# SCH.net
KiCad netlist of a schematic drawn in EasyEDA
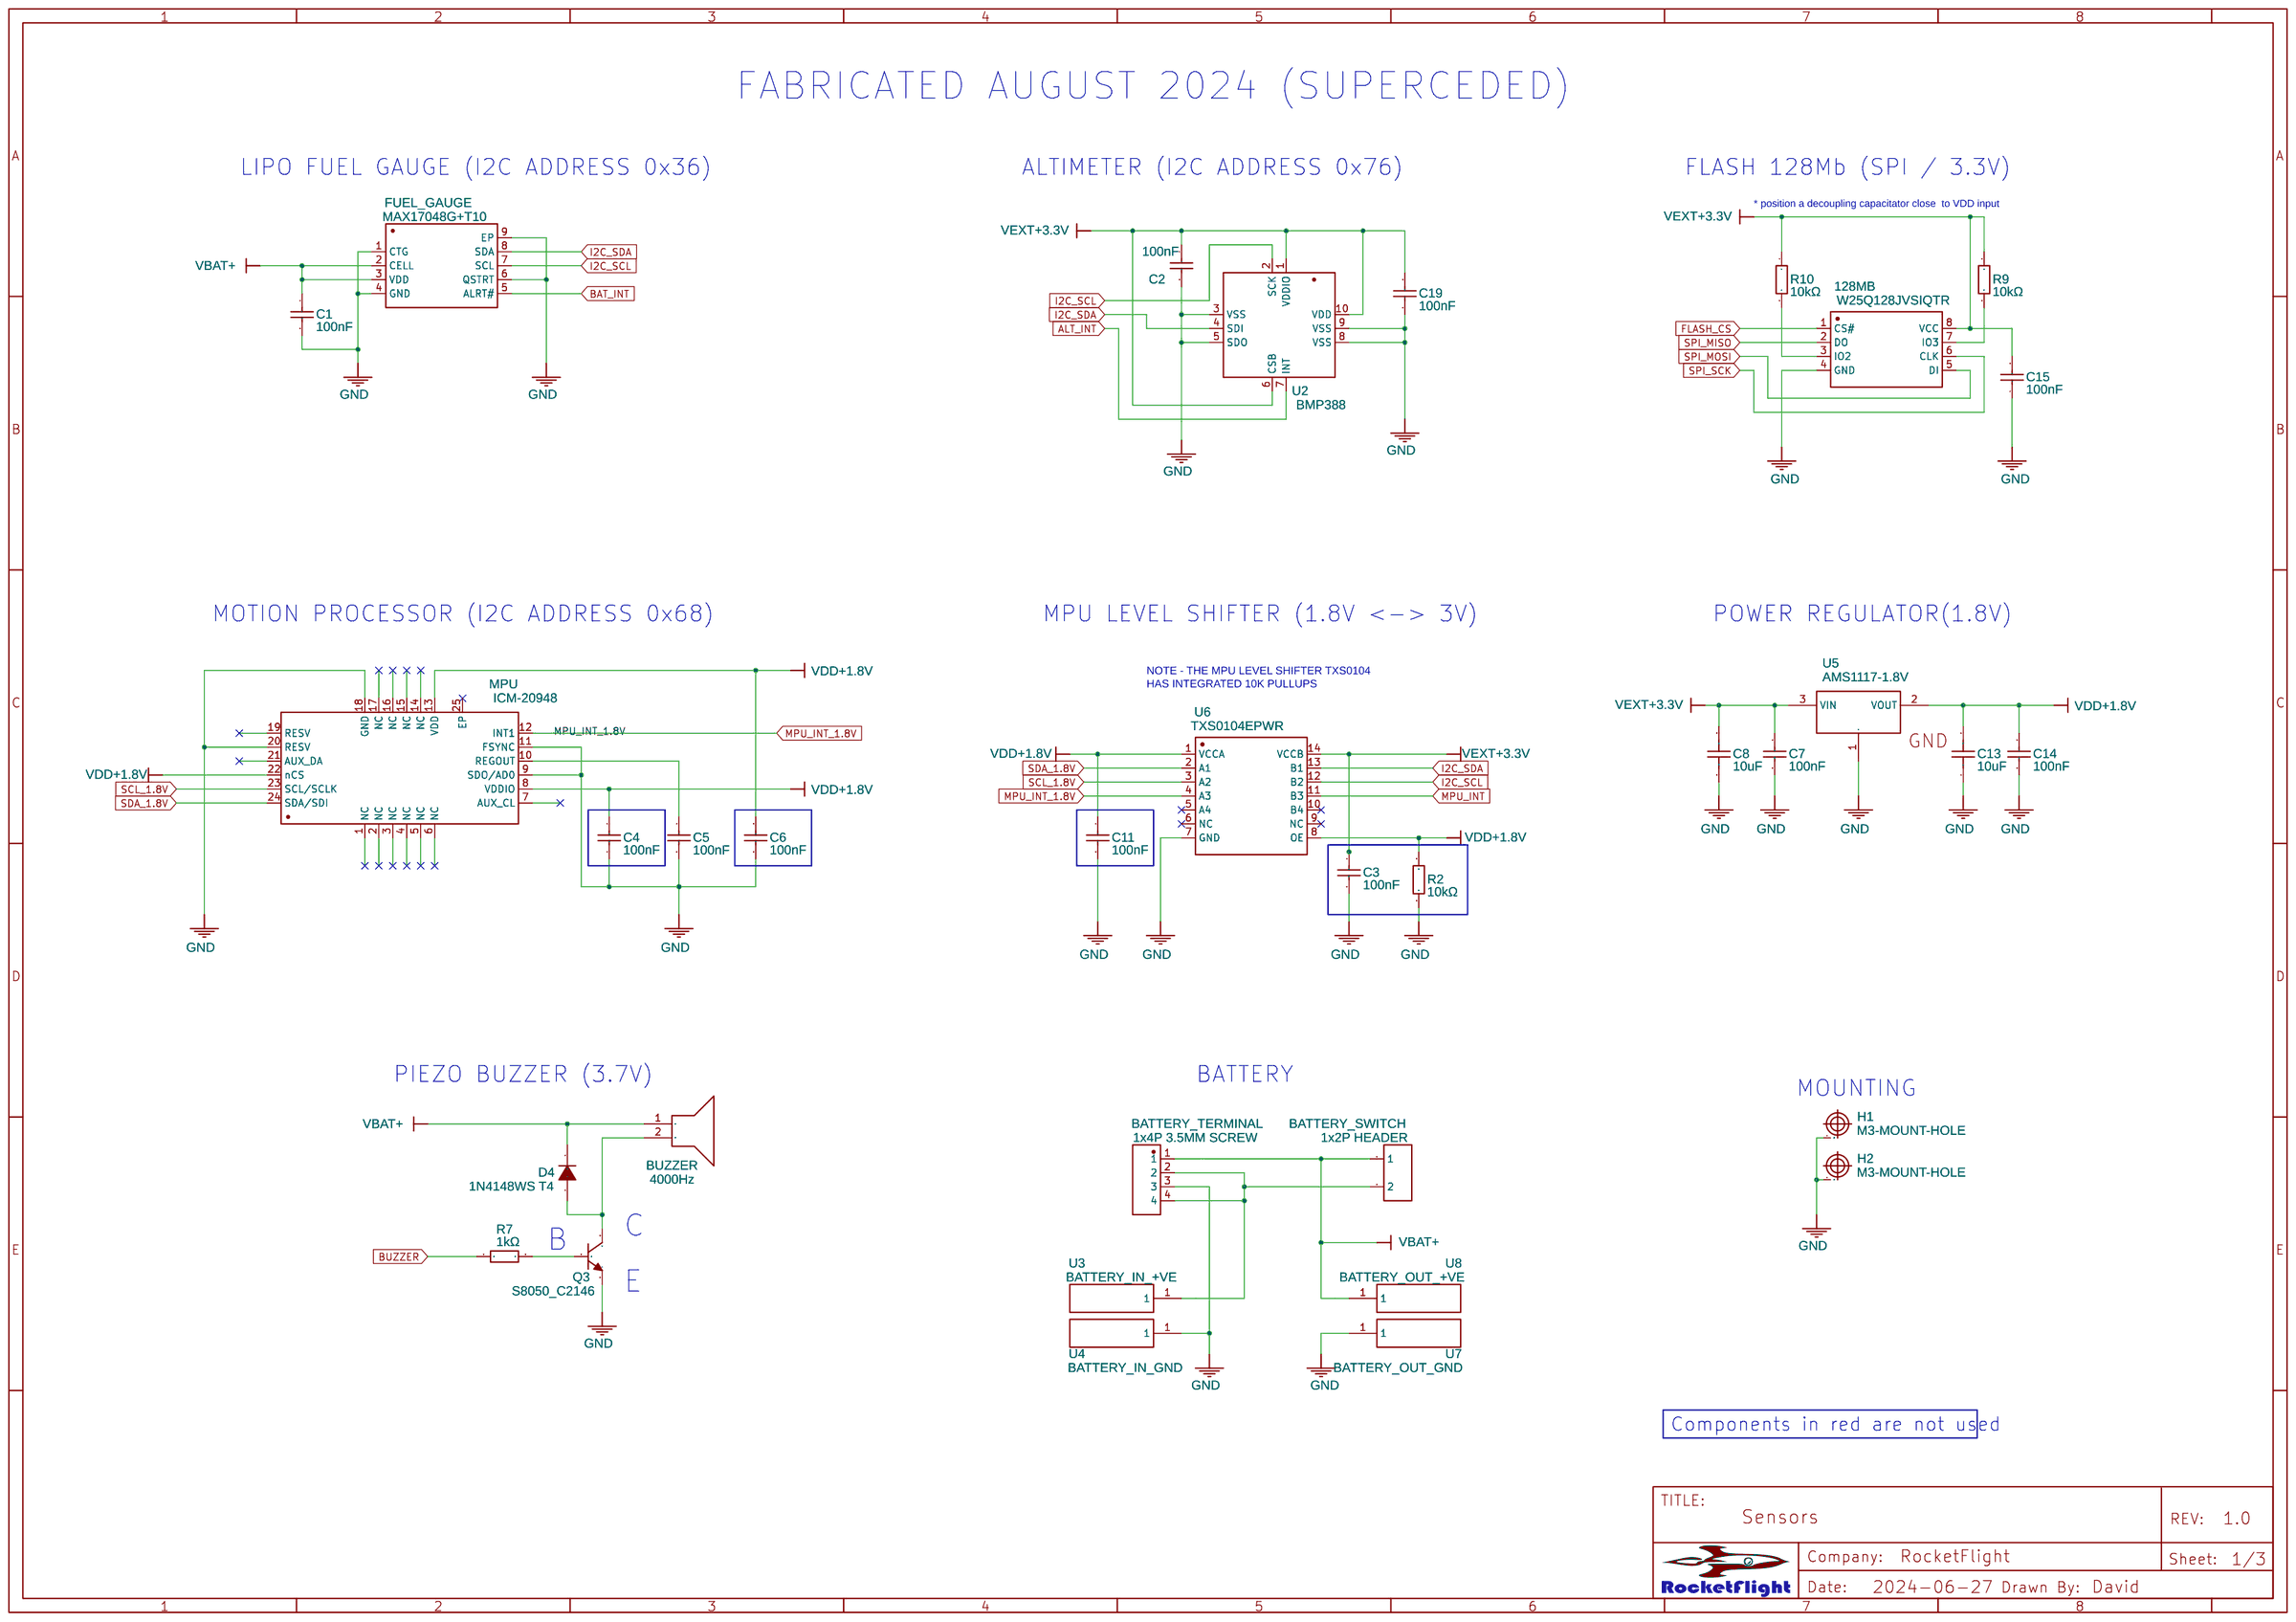
[diagram p0: Sensors]
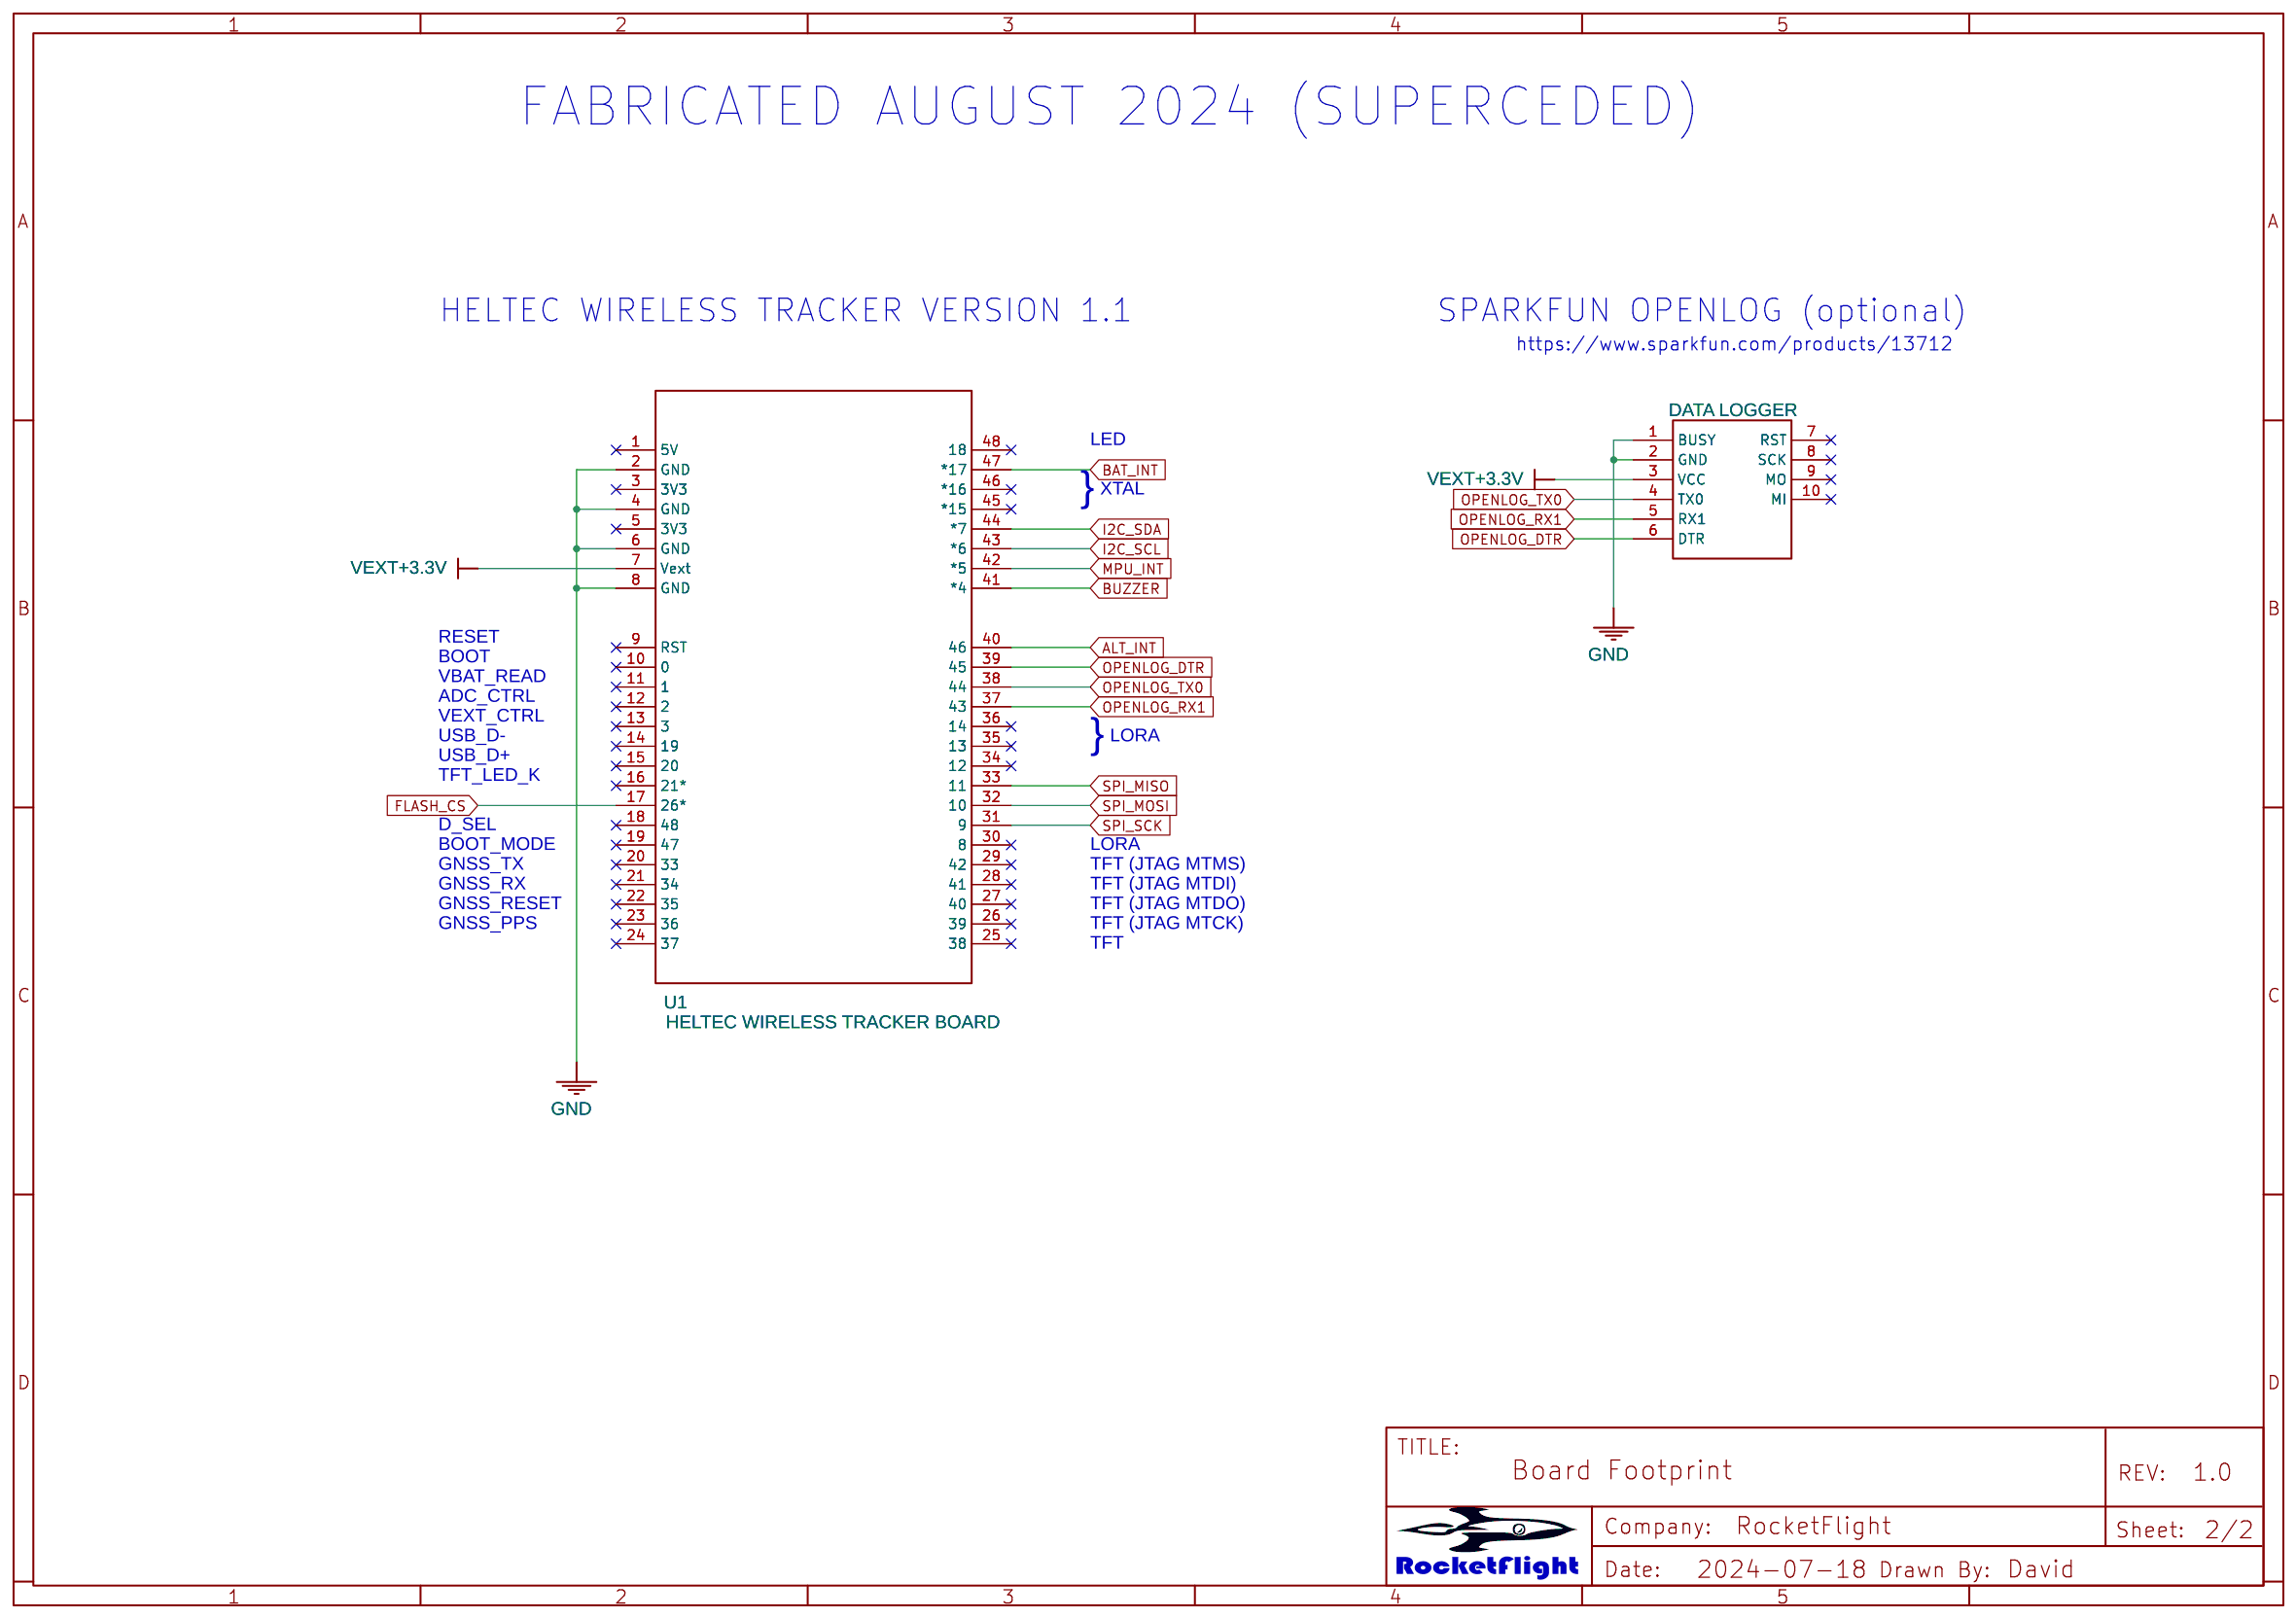
[diagram p1: Board]

(export (version "E")
  (design (tool "Eeschema 10.0.6"))
  (components
    (comp (ref "128MB")
      (value "W25Q128JVSIQTR")
      (fields (field (name "Manufacturer Part") "W25Q128JVSIQ") (field (name "Manufacturer") "WINBOND(华邦)"))
      (libsource (lib "") (part "W25Q128JVSIQTR"))
    )
    (comp (ref "BATTERY_SWITCH")
      (value "1x2P HEADER")
      (fields (field (name "Manufacturer Part") "826629-2") (field (name "Manufacturer") "TE Connectivity"))
      (libsource (lib "") (part "HDR-M-2.54_1X2_ROUND"))
    )
    (comp (ref "BATTERY_TERMINAL")
      (value "1x4P 3.5MM SCREW")
      (fields (field (name "Manufacturer Part") "XY350V-3.5-4P") (field (name "Manufacturer") "--"))
      (libsource (lib "") (part "XY350V-3.5-4P"))
    )
    (comp (ref "BUZZER")
      (value "4000Hz")
      (fields (field (name "Manufacturer Part") "FUET-9018") (field (name "Manufacturer") "FUET(福声科技)"))
      (libsource (lib "") (part "FST-9018 COPY"))
    )
    (comp (ref "C1")
      (value "100nF")
      (fields
        (field (name "Manufacturer Part") "CL05B104KO5NNNC")
        (field (name "Manufacturer") "SAMSUNG(三星)")
      )
      (libsource (lib "") (part "CL05B104KO5NNNC"))
    )
    (comp (ref "C2")
      (value "100nF")
      (fields
        (field (name "Manufacturer Part") "CL05B104KO5NNNC")
        (field (name "Manufacturer") "SAMSUNG(三星)")
      )
      (libsource (lib "") (part "CL05B104KO5NNNC"))
    )
    (comp (ref "C3")
      (value "100nF")
      (fields
        (field (name "Manufacturer Part") "CL05B104KO5NNNC")
        (field (name "Manufacturer") "SAMSUNG(三星)")
      )
      (libsource (lib "") (part "CL05B104KO5NNNC"))
    )
    (comp (ref "C4")
      (value "100nF")
      (fields
        (field (name "Manufacturer Part") "CL05B104KO5NNNC")
        (field (name "Manufacturer") "SAMSUNG(三星)")
      )
      (libsource (lib "") (part "CL05B104KO5NNNC_1"))
    )
    (comp (ref "C5")
      (value "100nF")
      (fields
        (field (name "Manufacturer Part") "CL05B104KO5NNNC")
        (field (name "Manufacturer") "SAMSUNG(三星)")
      )
      (libsource (lib "") (part "CL05B104KO5NNNC"))
    )
    (comp (ref "C6")
      (value "100nF")
      (fields
        (field (name "Manufacturer Part") "CL05B104KO5NNNC")
        (field (name "Manufacturer") "SAMSUNG(三星)")
      )
      (libsource (lib "") (part "CL05B104KO5NNNC_1"))
    )
    (comp (ref "C7")
      (value "100nF")
      (fields
        (field (name "Manufacturer Part") "CL05B104KO5NNNC")
        (field (name "Manufacturer") "SAMSUNG(三星)")
      )
      (libsource (lib "") (part "CL05B104KO5NNNC_1"))
    )
    (comp (ref "C8")
      (value "10uF")
      (fields
        (field (name "Manufacturer Part") "CL10A106MA8NRNC")
        (field (name "Manufacturer") "SAMSUNG(三星)")
      )
      (libsource (lib "") (part "CL10A106MA8NRNC"))
    )
    (comp (ref "C11")
      (value "100nF")
      (fields
        (field (name "Manufacturer Part") "CL05B104KO5NNNC")
        (field (name "Manufacturer") "SAMSUNG(三星)")
      )
      (libsource (lib "") (part "CL05B104KO5NNNC"))
    )
    (comp (ref "C13")
      (value "10uF")
      (fields
        (field (name "Manufacturer Part") "CL10A106MA8NRNC")
        (field (name "Manufacturer") "SAMSUNG(三星)")
      )
      (libsource (lib "") (part "CL10A106MA8NRNC"))
    )
    (comp (ref "C14")
      (value "100nF")
      (fields
        (field (name "Manufacturer Part") "CL05B104KO5NNNC")
        (field (name "Manufacturer") "SAMSUNG(三星)")
      )
      (libsource (lib "") (part "CL05B104KO5NNNC_1"))
    )
    (comp (ref "C15")
      (value "100nF")
      (fields
        (field (name "Manufacturer Part") "CL05B104KO5NNNC")
        (field (name "Manufacturer") "SAMSUNG(三星)")
      )
      (libsource (lib "") (part "CL05B104KO5NNNC_1"))
    )
    (comp (ref "C19")
      (value "100nF")
      (fields
        (field (name "Manufacturer Part") "CL05B104KO5NNNC")
        (field (name "Manufacturer") "SAMSUNG(三星)")
      )
      (libsource (lib "") (part "CL05B104KO5NNNC"))
    )
    (comp (ref "D4")
      (value "1N4148WS T4")
      (fields (field (name "Manufacturer Part") "1N4148WS") (field (name "Manufacturer") "CJ(江苏长电/长晶)"))
      (libsource (lib "") (part "1N4148WS T4"))
    )
    (comp (ref "FUEL_GAUGE")
      (value "MAX17048G+T10")
      (fields (field (name "Manufacturer") "ADI(亚德诺)/MAXIM(美信)"))
      (libsource (lib "") (part "MAX17048G+T10"))
    )
    (comp (ref "H1") (value "M3-MOUNT-HOLE") (libsource (lib "") (part "M3-MOUNT-HOLE")))
    (comp (ref "H2") (value "M3-MOUNT-HOLE") (libsource (lib "") (part "M3-MOUNT-HOLE")))
    (comp (ref "MPU")
      (value "ICM-20948")
      (fields (field (name "Manufacturer") "TDK InvenSense(应美盛)"))
      (libsource (lib "") (part "ICM-20948"))
    )
    (comp (ref "Q3")
      (value "S8050_C2146")
      (fields (field (name "Manufacturer Part") "S8050 J3Y") (field (name "Manufacturer") "CJ(江苏长电/长晶)"))
      (libsource (lib "") (part "S8050_C2146"))
    )
    (comp (ref "R2")
      (value "10kΩ")
      (fields
        (field (name "Manufacturer Part") "0402WGF1002TCE")
        (field (name "Manufacturer") "UNI-ROYAL(厚声)")
      )
      (libsource (lib "") (part "0402WGF1002TCE_1"))
    )
    (comp (ref "R7")
      (value "1kΩ")
      (fields
        (field (name "Manufacturer Part") "0603WAF1001T5E")
        (field (name "Manufacturer") "UNI-ROYAL(厚声)")
      )
      (libsource (lib "") (part "0603WAF1001T5E"))
    )
    (comp (ref "R9")
      (value "10kΩ")
      (fields
        (field (name "Manufacturer Part") "0402WGF1002TCE")
        (field (name "Manufacturer") "UNI-ROYAL(厚声)")
      )
      (libsource (lib "") (part "0402WGF1002TCE"))
    )
    (comp (ref "R10")
      (value "10kΩ")
      (fields
        (field (name "Manufacturer Part") "0402WGF1002TCE")
        (field (name "Manufacturer") "UNI-ROYAL(厚声)")
      )
      (libsource (lib "") (part "0402WGF1002TCE"))
    )
    (comp (ref "U2")
      (value "BMP388")
      (fields (field (name "Manufacturer") "Bosch(博世)"))
      (libsource (lib "") (part "BMP388"))
    )
    (comp (ref "U3")
      (value "BATTERY_IN_+VE")
      (fields (field (name "Manufacturer Part") "PAD_5.84mm×1.54mm×0.8mm"))
      (libsource (lib "") (part "MySolderPad1.5x2.5mm"))
    )
    (comp (ref "U4")
      (value "BATTERY_IN_GND")
      (fields (field (name "Manufacturer Part") "PAD_5.84mm×1.54mm×0.8mm"))
      (libsource (lib "") (part "MySolderPad1.5x2.5mm"))
    )
    (comp (ref "U5")
      (value "AMS1117-1.8V")
      (fields (field (name "Manufacturer") "MSKSEMI(美森科)"))
      (libsource (lib "") (part "AMS1117-1.8V"))
    )
    (comp (ref "U6")
      (value "TXS0104EPWR")
      (fields (field (name "Manufacturer") "TI(德州仪器)"))
      (libsource (lib "") (part "TXS0104EPWR"))
    )
    (comp (ref "U7")
      (value "BATTERY_OUT_GND")
      (fields (field (name "Manufacturer Part") "PAD_5.84mm×1.54mm×0.8mm"))
      (libsource (lib "") (part "MySolderPad1.5x2.5mm_1"))
    )
    (comp (ref "U8")
      (value "BATTERY_OUT_+VE")
      (fields (field (name "Manufacturer Part") "PAD_5.84mm×1.54mm×0.8mm"))
      (libsource (lib "") (part "MySolderPad1.5x2.5mm_1"))
    )
    (comp (ref "BUSY")
      (value "DATA LOGGER")
      (fields (field (name "Manufacturer Part") "Sparkfun"))
      (libsource (lib "") (part "DATA LOGGER_RN_OPENLOG COPY"))
    )
    (comp (ref "U1")
      (value "HELTEC WIRELESS TRACKER BOARD")
      (libsource (lib "") (part "HELTEC WIRELESS TRACKER BOARD"))
    )
  )
  (nets
    (net (code "1") (name "ALT_INT") (class "Default")
      (node (ref "U1") (pin "40") (pinfunction "46_40") (pintype "unspecified"))
      (node (ref "U2") (pin "7") (pinfunction "INT_7") (pintype "unspecified"))
    )
    (net (code "2") (name "BAT_INT") (class "Default")
      (node (ref "FUEL_GAUGE") (pin "5") (pinfunction "ALRT#_5") (pintype "unspecified"))
      (node (ref "U1") (pin "47") (pinfunction "*17_47") (pintype "unspecified"))
    )
    (net (code "3") (name "BUZZER") (class "Default")
      (node (ref "R7") (pin "1") (pinfunction "1_1") (pintype "input"))
      (node (ref "U1") (pin "41") (pinfunction "*4_41") (pintype "unspecified"))
    )
    (net (code "4") (name "FLASH_CS") (class "Default")
      (node (ref "128MB") (pin "1") (pinfunction "CS#_1") (pintype "unspecified"))
      (node (ref "U1") (pin "17") (pinfunction "26*_17") (pintype "unspecified"))
    )
    (net (code "5") (name "GND") (class "Default")
      (node (ref "128MB") (pin "4") (pinfunction "GND_4") (pintype "unspecified"))
      (node (ref "BATTERY_TERMINAL") (pin "3") (pinfunction "3_3") (pintype "unspecified"))
      (node (ref "BUSY") (pin "1") (pinfunction "BUSY_1") (pintype "unspecified"))
      (node (ref "BUSY") (pin "2") (pinfunction "GND_2") (pintype "unspecified"))
      (node (ref "C1") (pin "2") (pinfunction "2_2") (pintype "input"))
      (node (ref "C11") (pin "2") (pinfunction "2_2") (pintype "input"))
      (node (ref "C13") (pin "1") (pinfunction "1_1") (pintype "unspecified"))
      (node (ref "C14") (pin "1") (pinfunction "1_1") (pintype "input"))
      (node (ref "C15") (pin "1") (pinfunction "1_1") (pintype "input"))
      (node (ref "C19") (pin "2") (pinfunction "2_2") (pintype "input"))
      (node (ref "C2") (pin "2") (pinfunction "2_2") (pintype "input"))
      (node (ref "C3") (pin "2") (pinfunction "2_2") (pintype "input"))
      (node (ref "C4") (pin "1") (pinfunction "1_1") (pintype "input"))
      (node (ref "C5") (pin "2") (pinfunction "2_2") (pintype "input"))
      (node (ref "C6") (pin "1") (pinfunction "1_1") (pintype "input"))
      (node (ref "C7") (pin "1") (pinfunction "1_1") (pintype "input"))
      (node (ref "C8") (pin "1") (pinfunction "1_1") (pintype "unspecified"))
      (node (ref "FUEL_GAUGE") (pin "1") (pinfunction "CTG_1") (pintype "unspecified"))
      (node (ref "FUEL_GAUGE") (pin "4") (pinfunction "GND_4") (pintype "unspecified"))
      (node (ref "FUEL_GAUGE") (pin "6") (pinfunction "QSTRT_6") (pintype "unspecified"))
      (node (ref "FUEL_GAUGE") (pin "9") (pinfunction "EP_9") (pintype "unspecified"))
      (node (ref "H1") (pin "1") (pinfunction "GND_1") (pintype "passive"))
      (node (ref "H2") (pin "1") (pinfunction "GND_1") (pintype "passive"))
      (node (ref "MPU") (pin "11") (pinfunction "FSYNC_11") (pintype "unspecified"))
      (node (ref "MPU") (pin "18") (pinfunction "GND_18") (pintype "unspecified"))
      (node (ref "MPU") (pin "20") (pinfunction "RESV_20") (pintype "unspecified"))
      (node (ref "MPU") (pin "9") (pinfunction "SDO/AD0_9") (pintype "unspecified"))
      (node (ref "Q3") (pin "2") (pinfunction "E_2") (pintype "unspecified"))
      (node (ref "R2") (pin "1") (pinfunction "1_1") (pintype "input"))
      (node (ref "U1") (pin "2") (pinfunction "GND_2") (pintype "unspecified"))
      (node (ref "U1") (pin "4") (pinfunction "GND_4") (pintype "unspecified"))
      (node (ref "U1") (pin "6") (pinfunction "GND_6") (pintype "unspecified"))
      (node (ref "U1") (pin "8") (pinfunction "GND_8") (pintype "unspecified"))
      (node (ref "U2") (pin "3") (pinfunction "VSS_3") (pintype "unspecified"))
      (node (ref "U2") (pin "5") (pinfunction "SDO_5") (pintype "unspecified"))
      (node (ref "U2") (pin "8") (pinfunction "VSS_8") (pintype "unspecified"))
      (node (ref "U2") (pin "9") (pinfunction "VSS_9") (pintype "unspecified"))
      (node (ref "U4") (pin "1") (pinfunction "1_1") (pintype "unspecified"))
      (node (ref "U5") (pin "1") (pinfunction "GND_1") (pintype "passive"))
      (node (ref "U6") (pin "7") (pinfunction "GND_7") (pintype "unspecified"))
      (node (ref "U7") (pin "1") (pinfunction "1_1") (pintype "unspecified"))
    )
    (net (code "6") (name "I2C_SCL") (class "Default")
      (node (ref "FUEL_GAUGE") (pin "7") (pinfunction "SCL_7") (pintype "unspecified"))
      (node (ref "U1") (pin "43") (pinfunction "*6_43") (pintype "unspecified"))
      (node (ref "U2") (pin "2") (pinfunction "SCK_2") (pintype "unspecified"))
      (node (ref "U6") (pin "12") (pinfunction "B2_12") (pintype "unspecified"))
    )
    (net (code "7") (name "I2C_SDA") (class "Default")
      (node (ref "FUEL_GAUGE") (pin "8") (pinfunction "SDA_8") (pintype "unspecified"))
      (node (ref "U1") (pin "44") (pinfunction "*7_44") (pintype "unspecified"))
      (node (ref "U2") (pin "4") (pinfunction "SDI_4") (pintype "unspecified"))
      (node (ref "U6") (pin "13") (pinfunction "B1_13") (pintype "unspecified"))
    )
    (net (code "8") (name "MPU_INT") (class "Default")
      (node (ref "U1") (pin "42") (pinfunction "*5_42") (pintype "unspecified"))
      (node (ref "U6") (pin "11") (pinfunction "B3_11") (pintype "unspecified"))
    )
    (net (code "9") (name "MPU_INT_1.8V") (class "Default")
      (node (ref "MPU") (pin "12") (pinfunction "INT1_12") (pintype "unspecified"))
      (node (ref "U6") (pin "4") (pinfunction "A3_4") (pintype "unspecified"))
    )
    (net (code "10") (name "Net-(128MB-IO2)") (class "Default")
      (node (ref "128MB") (pin "3") (pinfunction "IO2_3") (pintype "unspecified"))
      (node (ref "R10") (pin "2") (pinfunction "2_2") (pintype "input"))
    )
    (net (code "11") (name "Net-(128MB-IO3)") (class "Default")
      (node (ref "128MB") (pin "7") (pinfunction "IO3_7") (pintype "unspecified"))
      (node (ref "R9") (pin "2") (pinfunction "2_2") (pintype "input"))
    )
    (net (code "12") (name "Net-(BATTERY_SWITCH-Pad2)") (class "Default")
      (node (ref "BATTERY_SWITCH") (pin "2") (pinfunction "2_2") (pintype "unspecified"))
      (node (ref "BATTERY_TERMINAL") (pin "2") (pinfunction "2_2") (pintype "unspecified"))
      (node (ref "BATTERY_TERMINAL") (pin "4") (pinfunction "4_4") (pintype "unspecified"))
      (node (ref "U3") (pin "1") (pinfunction "1_1") (pintype "unspecified"))
    )
    (net (code "13") (name "Net-(D4-A)") (class "Default")
      (node (ref "BUZZER") (pin "2") (pinfunction "2_2") (pintype "unspecified"))
      (node (ref "D4") (pin "2") (pinfunction "A_2") (pintype "unspecified"))
      (node (ref "Q3") (pin "3") (pinfunction "C_3") (pintype "unspecified"))
    )
    (net (code "14") (name "Net-(MPU-REGOUT)") (class "Default")
      (node (ref "C5") (pin "1") (pinfunction "1_1") (pintype "input"))
      (node (ref "MPU") (pin "10") (pinfunction "REGOUT_10") (pintype "unspecified"))
    )
    (net (code "15") (name "Net-(Q3-B)") (class "Default")
      (node (ref "Q3") (pin "1") (pinfunction "B_1") (pintype "unspecified"))
      (node (ref "R7") (pin "2") (pinfunction "2_2") (pintype "input"))
    )
    (net (code "16") (name "OPENLOG_DTR") (class "Default")
      (node (ref "BUSY") (pin "6") (pinfunction "DTR_6") (pintype "unspecified"))
      (node (ref "U1") (pin "39") (pinfunction "45_39") (pintype "unspecified"))
    )
    (net (code "17") (name "OPENLOG_RX1") (class "Default")
      (node (ref "BUSY") (pin "5") (pinfunction "RX1_5") (pintype "unspecified"))
      (node (ref "U1") (pin "37") (pinfunction "43_37") (pintype "unspecified"))
    )
    (net (code "18") (name "OPENLOG_TX0") (class "Default")
      (node (ref "BUSY") (pin "4") (pinfunction "TX0_4") (pintype "unspecified"))
      (node (ref "U1") (pin "38") (pinfunction "44_38") (pintype "unspecified"))
    )
    (net (code "19") (name "SCL_1.8V") (class "Default")
      (node (ref "MPU") (pin "23") (pinfunction "SCL/SCLK_23") (pintype "unspecified"))
      (node (ref "U6") (pin "3") (pinfunction "A2_3") (pintype "unspecified"))
    )
    (net (code "20") (name "SDA_1.8V") (class "Default")
      (node (ref "MPU") (pin "24") (pinfunction "SDA/SDI_24") (pintype "unspecified"))
      (node (ref "U6") (pin "2") (pinfunction "A1_2") (pintype "unspecified"))
    )
    (net (code "21") (name "SPI_MISO") (class "Default")
      (node (ref "128MB") (pin "2") (pinfunction "DO_2") (pintype "unspecified"))
      (node (ref "U1") (pin "33") (pinfunction "11_33") (pintype "unspecified"))
    )
    (net (code "22") (name "SPI_MOSI") (class "Default")
      (node (ref "128MB") (pin "5") (pinfunction "DI_5") (pintype "unspecified"))
      (node (ref "U1") (pin "32") (pinfunction "10_32") (pintype "unspecified"))
    )
    (net (code "23") (name "SPI_SCK") (class "Default")
      (node (ref "128MB") (pin "6") (pinfunction "CLK_6") (pintype "unspecified"))
      (node (ref "U1") (pin "31") (pinfunction "9_31") (pintype "unspecified"))
    )
    (net (code "24") (name "VBAT+") (class "Default")
      (node (ref "BATTERY_SWITCH") (pin "1") (pinfunction "1_1") (pintype "unspecified"))
      (node (ref "BATTERY_TERMINAL") (pin "1") (pinfunction "1_1") (pintype "unspecified"))
      (node (ref "BUZZER") (pin "1") (pinfunction "1_1") (pintype "unspecified"))
      (node (ref "C1") (pin "1") (pinfunction "1_1") (pintype "input"))
      (node (ref "D4") (pin "1") (pinfunction "K_1") (pintype "unspecified"))
      (node (ref "FUEL_GAUGE") (pin "2") (pinfunction "CELL_2") (pintype "unspecified"))
      (node (ref "FUEL_GAUGE") (pin "3") (pinfunction "VDD_3") (pintype "unspecified"))
      (node (ref "U8") (pin "1") (pinfunction "1_1") (pintype "unspecified"))
    )
    (net (code "25") (name "VDD+1.8V") (class "Default")
      (node (ref "C11") (pin "1") (pinfunction "1_1") (pintype "input"))
      (node (ref "C13") (pin "2") (pinfunction "2_2") (pintype "unspecified"))
      (node (ref "C14") (pin "2") (pinfunction "2_2") (pintype "input"))
      (node (ref "C4") (pin "2") (pinfunction "2_2") (pintype "input"))
      (node (ref "C6") (pin "2") (pinfunction "2_2") (pintype "input"))
      (node (ref "MPU") (pin "13") (pinfunction "VDD_13") (pintype "unspecified"))
      (node (ref "MPU") (pin "22") (pinfunction "nCS_22") (pintype "unspecified"))
      (node (ref "MPU") (pin "8") (pinfunction "VDDIO_8") (pintype "unspecified"))
      (node (ref "R2") (pin "2") (pinfunction "2_2") (pintype "input"))
      (node (ref "U5") (pin "2") (pinfunction "VOUT_2") (pintype "passive"))
      (node (ref "U6") (pin "1") (pinfunction "VCCA_1") (pintype "unspecified"))
      (node (ref "U6") (pin "8") (pinfunction "OE_8") (pintype "unspecified"))
    )
    (net (code "26") (name "VEXT+3.3V") (class "Default")
      (node (ref "128MB") (pin "8") (pinfunction "VCC_8") (pintype "unspecified"))
      (node (ref "BUSY") (pin "3") (pinfunction "VCC_3") (pintype "unspecified"))
      (node (ref "C15") (pin "2") (pinfunction "2_2") (pintype "input"))
      (node (ref "C19") (pin "1") (pinfunction "1_1") (pintype "input"))
      (node (ref "C2") (pin "1") (pinfunction "1_1") (pintype "input"))
      (node (ref "C3") (pin "1") (pinfunction "1_1") (pintype "input"))
      (node (ref "C7") (pin "2") (pinfunction "2_2") (pintype "input"))
      (node (ref "C8") (pin "2") (pinfunction "2_2") (pintype "unspecified"))
      (node (ref "R10") (pin "1") (pinfunction "1_1") (pintype "input"))
      (node (ref "R9") (pin "1") (pinfunction "1_1") (pintype "input"))
      (node (ref "U1") (pin "7") (pinfunction "Vext_7") (pintype "unspecified"))
      (node (ref "U2") (pin "1") (pinfunction "VDDIO_1") (pintype "unspecified"))
      (node (ref "U2") (pin "10") (pinfunction "VDD_10") (pintype "unspecified"))
      (node (ref "U2") (pin "6") (pinfunction "CSB_6") (pintype "unspecified"))
      (node (ref "U5") (pin "3") (pinfunction "VIN_3") (pintype "passive"))
      (node (ref "U6") (pin "14") (pinfunction "VCCB_14") (pintype "unspecified"))
    )
    (net (code "27") (name "unconnected-(BUSY-MI-Pad10)") (class "Default")
      (node (ref "BUSY") (pin "10") (pinfunction "MI_10") (pintype "unspecified+no_connect"))
    )
    (net (code "28") (name "unconnected-(BUSY-MO-Pad9)") (class "Default")
      (node (ref "BUSY") (pin "9") (pinfunction "MO_9") (pintype "unspecified+no_connect"))
    )
    (net (code "29") (name "unconnected-(BUSY-RST-Pad7)") (class "Default")
      (node (ref "BUSY") (pin "7") (pinfunction "RST_7") (pintype "unspecified+no_connect"))
    )
    (net (code "30") (name "unconnected-(BUSY-SCK-Pad8)") (class "Default")
      (node (ref "BUSY") (pin "8") (pinfunction "SCK_8") (pintype "unspecified+no_connect"))
    )
    (net (code "31") (name "unconnected-(MPU-AUX_CL-Pad7)") (class "Default")
      (node (ref "MPU") (pin "7") (pinfunction "AUX_CL_7") (pintype "unspecified+no_connect"))
    )
    (net (code "32") (name "unconnected-(MPU-AUX_DA-Pad21)") (class "Default")
      (node (ref "MPU") (pin "21") (pinfunction "AUX_DA_21") (pintype "unspecified+no_connect"))
    )
    (net (code "33") (name "unconnected-(MPU-EP-Pad25)") (class "Default")
      (node (ref "MPU") (pin "25") (pinfunction "EP_25") (pintype "unspecified+no_connect"))
    )
    (net (code "34") (name "unconnected-(MPU-NC-Pad1)") (class "Default")
      (node (ref "MPU") (pin "1") (pinfunction "NC_1") (pintype "unspecified+no_connect"))
    )
    (net (code "35") (name "unconnected-(MPU-NC-Pad2)") (class "Default")
      (node (ref "MPU") (pin "2") (pinfunction "NC_2") (pintype "unspecified+no_connect"))
    )
    (net (code "36") (name "unconnected-(MPU-NC-Pad3)") (class "Default")
      (node (ref "MPU") (pin "3") (pinfunction "NC_3") (pintype "unspecified+no_connect"))
    )
    (net (code "37") (name "unconnected-(MPU-NC-Pad4)") (class "Default")
      (node (ref "MPU") (pin "4") (pinfunction "NC_4") (pintype "unspecified+no_connect"))
    )
    (net (code "38") (name "unconnected-(MPU-NC-Pad5)") (class "Default")
      (node (ref "MPU") (pin "5") (pinfunction "NC_5") (pintype "unspecified+no_connect"))
    )
    (net (code "39") (name "unconnected-(MPU-NC-Pad6)") (class "Default")
      (node (ref "MPU") (pin "6") (pinfunction "NC_6") (pintype "unspecified+no_connect"))
    )
    (net (code "40") (name "unconnected-(MPU-NC-Pad14)") (class "Default")
      (node (ref "MPU") (pin "14") (pinfunction "NC_14") (pintype "unspecified+no_connect"))
    )
    (net (code "41") (name "unconnected-(MPU-NC-Pad15)") (class "Default")
      (node (ref "MPU") (pin "15") (pinfunction "NC_15") (pintype "unspecified+no_connect"))
    )
    (net (code "42") (name "unconnected-(MPU-NC-Pad16)") (class "Default")
      (node (ref "MPU") (pin "16") (pinfunction "NC_16") (pintype "unspecified+no_connect"))
    )
    (net (code "43") (name "unconnected-(MPU-NC-Pad17)") (class "Default")
      (node (ref "MPU") (pin "17") (pinfunction "NC_17") (pintype "unspecified+no_connect"))
    )
    (net (code "44") (name "unconnected-(MPU-RESV-Pad19)") (class "Default")
      (node (ref "MPU") (pin "19") (pinfunction "RESV_19") (pintype "unspecified+no_connect"))
    )
    (net (code "45") (name "unconnected-(U1-*15-Pad45)") (class "Default")
      (node (ref "U1") (pin "45") (pinfunction "*15_45") (pintype "unspecified+no_connect"))
    )
    (net (code "46") (name "unconnected-(U1-*16-Pad46)") (class "Default")
      (node (ref "U1") (pin "46") (pinfunction "*16_46") (pintype "unspecified+no_connect"))
    )
    (net (code "47") (name "unconnected-(U1-0-Pad10)") (class "Default")
      (node (ref "U1") (pin "10") (pinfunction "0_10") (pintype "unspecified+no_connect"))
    )
    (net (code "48") (name "unconnected-(U1-1-Pad11)") (class "Default")
      (node (ref "U1") (pin "11") (pinfunction "1_11") (pintype "unspecified+no_connect"))
    )
    (net (code "49") (name "unconnected-(U1-2-Pad12)") (class "Default")
      (node (ref "U1") (pin "12") (pinfunction "2_12") (pintype "unspecified+no_connect"))
    )
    (net (code "50") (name "unconnected-(U1-3-Pad13)") (class "Default")
      (node (ref "U1") (pin "13") (pinfunction "3_13") (pintype "unspecified+no_connect"))
    )
    (net (code "51") (name "unconnected-(U1-3V3-Pad3)") (class "Default")
      (node (ref "U1") (pin "3") (pinfunction "3V3_3") (pintype "unspecified+no_connect"))
    )
    (net (code "52") (name "unconnected-(U1-3V3-Pad5)") (class "Default")
      (node (ref "U1") (pin "5") (pinfunction "3V3_5") (pintype "unspecified+no_connect"))
    )
    (net (code "53") (name "unconnected-(U1-5V-Pad1)") (class "Default")
      (node (ref "U1") (pin "1") (pinfunction "5V_1") (pintype "unspecified+no_connect"))
    )
    (net (code "54") (name "unconnected-(U1-8-Pad30)") (class "Default")
      (node (ref "U1") (pin "30") (pinfunction "8_30") (pintype "unspecified+no_connect"))
    )
    (net (code "55") (name "unconnected-(U1-12-Pad34)") (class "Default")
      (node (ref "U1") (pin "34") (pinfunction "12_34") (pintype "unspecified+no_connect"))
    )
    (net (code "56") (name "unconnected-(U1-13-Pad35)") (class "Default")
      (node (ref "U1") (pin "35") (pinfunction "13_35") (pintype "unspecified+no_connect"))
    )
    (net (code "57") (name "unconnected-(U1-14-Pad36)") (class "Default")
      (node (ref "U1") (pin "36") (pinfunction "14_36") (pintype "unspecified+no_connect"))
    )
    (net (code "58") (name "unconnected-(U1-18-Pad48)") (class "Default")
      (node (ref "U1") (pin "48") (pinfunction "18_48") (pintype "unspecified+no_connect"))
    )
    (net (code "59") (name "unconnected-(U1-19-Pad14)") (class "Default")
      (node (ref "U1") (pin "14") (pinfunction "19_14") (pintype "unspecified+no_connect"))
    )
    (net (code "60") (name "unconnected-(U1-20-Pad15)") (class "Default")
      (node (ref "U1") (pin "15") (pinfunction "20_15") (pintype "unspecified+no_connect"))
    )
    (net (code "61") (name "unconnected-(U1-21*-Pad16)") (class "Default")
      (node (ref "U1") (pin "16") (pinfunction "21*_16") (pintype "unspecified+no_connect"))
    )
    (net (code "62") (name "unconnected-(U1-33-Pad20)") (class "Default")
      (node (ref "U1") (pin "20") (pinfunction "33_20") (pintype "unspecified+no_connect"))
    )
    (net (code "63") (name "unconnected-(U1-34-Pad21)") (class "Default")
      (node (ref "U1") (pin "21") (pinfunction "34_21") (pintype "unspecified+no_connect"))
    )
    (net (code "64") (name "unconnected-(U1-35-Pad22)") (class "Default")
      (node (ref "U1") (pin "22") (pinfunction "35_22") (pintype "unspecified+no_connect"))
    )
    (net (code "65") (name "unconnected-(U1-36-Pad23)") (class "Default")
      (node (ref "U1") (pin "23") (pinfunction "36_23") (pintype "unspecified+no_connect"))
    )
    (net (code "66") (name "unconnected-(U1-37-Pad24)") (class "Default")
      (node (ref "U1") (pin "24") (pinfunction "37_24") (pintype "unspecified+no_connect"))
    )
    (net (code "67") (name "unconnected-(U1-38-Pad25)") (class "Default")
      (node (ref "U1") (pin "25") (pinfunction "38_25") (pintype "unspecified+no_connect"))
    )
    (net (code "68") (name "unconnected-(U1-39-Pad26)") (class "Default")
      (node (ref "U1") (pin "26") (pinfunction "39_26") (pintype "unspecified+no_connect"))
    )
    (net (code "69") (name "unconnected-(U1-40-Pad27)") (class "Default")
      (node (ref "U1") (pin "27") (pinfunction "40_27") (pintype "unspecified+no_connect"))
    )
    (net (code "70") (name "unconnected-(U1-41-Pad28)") (class "Default")
      (node (ref "U1") (pin "28") (pinfunction "41_28") (pintype "unspecified+no_connect"))
    )
    (net (code "71") (name "unconnected-(U1-42-Pad29)") (class "Default")
      (node (ref "U1") (pin "29") (pinfunction "42_29") (pintype "unspecified+no_connect"))
    )
    (net (code "72") (name "unconnected-(U1-47-Pad19)") (class "Default")
      (node (ref "U1") (pin "19") (pinfunction "47_19") (pintype "unspecified+no_connect"))
    )
    (net (code "73") (name "unconnected-(U1-48-Pad18)") (class "Default")
      (node (ref "U1") (pin "18") (pinfunction "48_18") (pintype "unspecified+no_connect"))
    )
    (net (code "74") (name "unconnected-(U1-RST-Pad9)") (class "Default")
      (node (ref "U1") (pin "9") (pinfunction "RST_9") (pintype "unspecified+no_connect"))
    )
    (net (code "75") (name "unconnected-(U6-A4-Pad5)") (class "Default")
      (node (ref "U6") (pin "5") (pinfunction "A4_5") (pintype "unspecified+no_connect"))
    )
    (net (code "76") (name "unconnected-(U6-B4-Pad10)") (class "Default")
      (node (ref "U6") (pin "10") (pinfunction "B4_10") (pintype "unspecified+no_connect"))
    )
    (net (code "77") (name "unconnected-(U6-NC-Pad6)") (class "Default")
      (node (ref "U6") (pin "6") (pinfunction "NC_6") (pintype "unspecified+no_connect"))
    )
    (net (code "78") (name "unconnected-(U6-NC-Pad9)") (class "Default")
      (node (ref "U6") (pin "9") (pinfunction "NC_9") (pintype "unspecified+no_connect"))
    )
  )
)
